# tdlf_server_top_modulaire.net
KiCad netlist of a schematic drawn in EAGLE
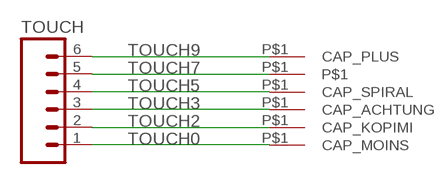
[diagram p0: schematic, sheet 1]

(export (version "E")
  (design (tool "Eeschema 10.0.6"))
  (components
    (comp (ref "CAP_MUSH")
      (value "MUSH")
      (footprint "eagle-import:TDLF_CAP_02")
      (libsource (lib "eagle-import") (part "TDLF_CAP_02"))
    )
    (comp (ref "CAP_PLUS")
      (value "TDLF_CAP_PLUS")
      (footprint "eagle-import:TDLF_CAP_PLUS")
      (libsource (lib "eagle-import") (part "TDLF_CAP_PLUS"))
    )
    (comp (ref "TOUCH")
      (value "M06SMD-STRAIGHT-COMBO-FEMALE")
      (footprint "eagle-import:1X06_SMD_STRAIGHT_COMBO")
      (libsource (lib "eagle-import") (part "M06SMD-STRAIGHT-COMBO-FEMALE"))
    )
    (comp (ref "U$1")
      (value "TDLF_CAP_MOINS")
      (footprint "eagle-import:TDLF_CAP_MOINS")
      (libsource (lib "eagle-import") (part "TDLF_CAP_MOINS"))
    )
    (comp (ref "U$2")
      (value "TDLF_CAP_SPIRAL")
      (footprint "eagle-import:TDLF_CAP_SPIRAL")
      (libsource (lib "eagle-import") (part "TDLF_CAP_SPIRAL"))
    )
    (comp (ref "U$3")
      (value "TDLF_CAP_KOPIMI")
      (footprint "eagle-import:TDLF_CAP_KOPIMI")
      (libsource (lib "eagle-import") (part "TDLF_CAP_KOPIMI"))
    )
    (comp (ref "U$4")
      (value "TDLF_CAP_ACHTUNG")
      (footprint "eagle-import:TDLF_CAP_ACHTUNG")
      (libsource (lib "eagle-import") (part "TDLF_CAP_ACHTUNG"))
    )
  )
  (nets
    (net (code "1") (name "/TOUCH0") (class "Default")
      (node (ref "TOUCH") (pin "1") (pinfunction "1_1") (pintype "passive"))
      (node (ref "U$1") (pin "P$1") (pinfunction "CAP_MOINS_P$1") (pintype "bidirectional"))
    )
    (net (code "2") (name "/TOUCH2") (class "Default")
      (node (ref "TOUCH") (pin "2") (pinfunction "2_2") (pintype "passive"))
      (node (ref "U$3") (pin "P$1") (pinfunction "CAP_KOPIMI_P$1") (pintype "bidirectional"))
    )
    (net (code "3") (name "/TOUCH3") (class "Default")
      (node (ref "TOUCH") (pin "3") (pinfunction "3_3") (pintype "passive"))
      (node (ref "U$4") (pin "P$1") (pinfunction "CAP_ACHTUNG_P$1") (pintype "bidirectional"))
    )
    (net (code "4") (name "/TOUCH5") (class "Default")
      (node (ref "TOUCH") (pin "4") (pinfunction "4_4") (pintype "passive"))
      (node (ref "U$2") (pin "P$1") (pinfunction "CAP_SPIRAL_P$1") (pintype "bidirectional"))
    )
    (net (code "5") (name "/TOUCH7") (class "Default")
      (node (ref "CAP_MUSH") (pin "P$1") (pinfunction "P$1_P$1") (pintype "bidirectional"))
      (node (ref "TOUCH") (pin "5") (pinfunction "5_5") (pintype "passive"))
    )
    (net (code "6") (name "/TOUCH9") (class "Default")
      (node (ref "CAP_PLUS") (pin "P$1") (pinfunction "CAP_PLUS_P$1") (pintype "bidirectional"))
      (node (ref "TOUCH") (pin "6") (pinfunction "6_6") (pintype "passive"))
    )
  )
)
